# SCH_AOG_Test_Board_2023-11-28.net
KiCad netlist of a schematic drawn in EasyEDA
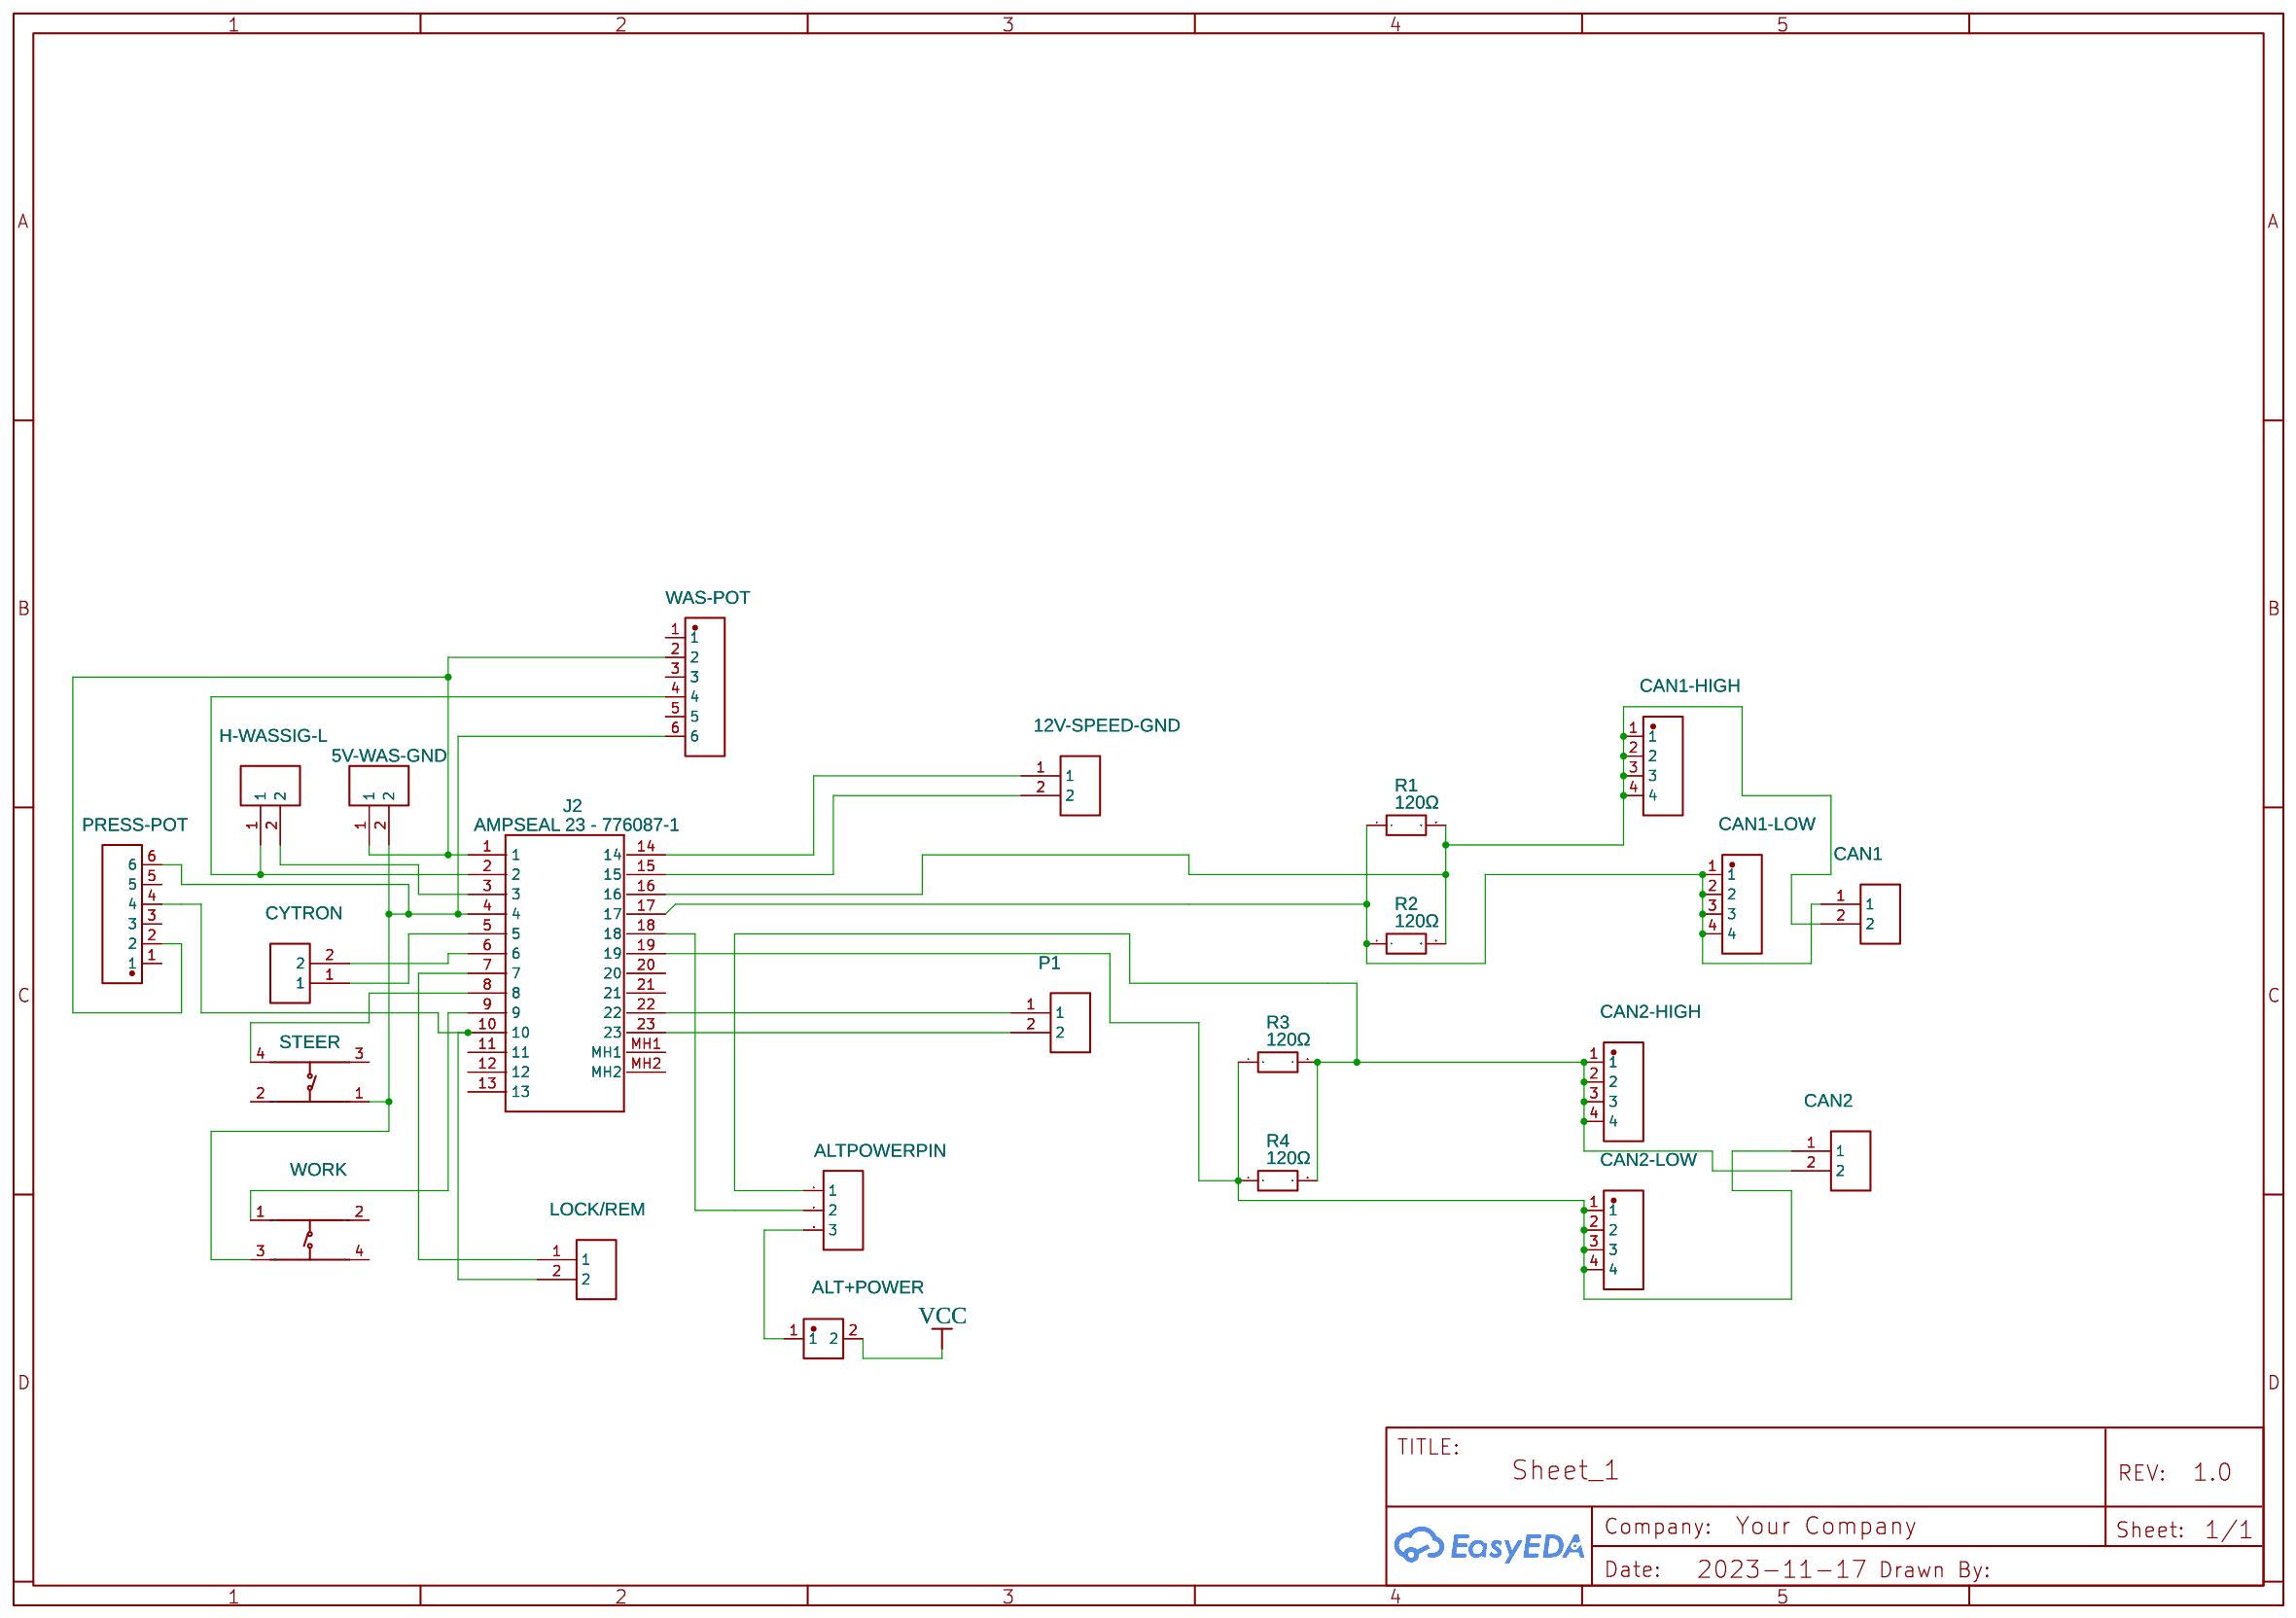
[diagram p0: schematic sheet]

(export (version "E")
  (design (tool "Eeschema 10.0.6"))
  (components
    (comp (ref "5V-WAS-GND")
      (value "WJ500V-5.08-2P-14-00A")
      (fields
        (field (name "Manufacturer Part") "WJ500V-5.08-2P")
        (field (name "Manufacturer") "KANGNEX(康奈克斯电气)")
      )
      (libsource (lib "") (part "WJ500V-5.08-2P-14-00A_3"))
    )
    (comp (ref "12V-SPEED-GND")
      (value "WJ500V-5.08-2P-14-00A")
      (fields
        (field (name "Manufacturer Part") "WJ500V-5.08-2P")
        (field (name "Manufacturer") "KANGNEX(康奈克斯电气)")
      )
      (libsource (lib "") (part "WJ500V-5.08-2P-14-00A_5"))
    )
    (comp (ref "ALT+POWER")
      (value "EST026")
      (fields (field (name "Manufacturer") "xcfuse(旭程)"))
      (libsource (lib "") (part "EST026"))
    )
    (comp (ref "ALTPOWERPIN")
      (value "Header-Male-2.54_1x3")
      (fields (field (name "Manufacturer Part") "2.54-1*3P针") (field (name "Manufacturer") "BOOMELE(博穆精密)"))
      (libsource (lib "") (part "Header-Male-2.54_1x3"))
    )
    (comp (ref "CAN1")
      (value "WJ500V-5.08-2P-14-00A")
      (fields
        (field (name "Manufacturer Part") "WJ500V-5.08-2P")
        (field (name "Manufacturer") "KANGNEX(康奈克斯电气)")
      )
      (libsource (lib "") (part "WJ500V-5.08-2P-14-00A_1"))
    )
    (comp (ref "CAN1-HIGH")
      (value "BX-PZ2.54-1-4PZZ")
      (fields (field (name "Manufacturer") "Bossie(博锡)"))
      (libsource (lib "") (part "BX-PZ2.54-1-4PZZ"))
    )
    (comp (ref "CAN1-LOW")
      (value "BX-PZ2.54-1-4PZZ")
      (fields (field (name "Manufacturer") "Bossie(博锡)"))
      (libsource (lib "") (part "BX-PZ2.54-1-4PZZ_3"))
    )
    (comp (ref "CAN2")
      (value "WJ500V-5.08-2P-14-00A")
      (fields
        (field (name "Manufacturer Part") "WJ500V-5.08-2P")
        (field (name "Manufacturer") "KANGNEX(康奈克斯电气)")
      )
      (libsource (lib "") (part "WJ500V-5.08-2P-14-00A_1"))
    )
    (comp (ref "CAN2-HIGH")
      (value "BX-PZ2.54-1-4PZZ")
      (fields (field (name "Manufacturer") "Bossie(博锡)"))
      (libsource (lib "") (part "BX-PZ2.54-1-4PZZ_1"))
    )
    (comp (ref "CAN2-LOW")
      (value "BX-PZ2.54-1-4PZZ")
      (fields (field (name "Manufacturer") "Bossie(博锡)"))
      (libsource (lib "") (part "BX-PZ2.54-1-4PZZ_2"))
    )
    (comp (ref "CYTRON")
      (value "WJ500V-5.08-2P-14-00A")
      (fields
        (field (name "Manufacturer Part") "WJ500V-5.08-2P")
        (field (name "Manufacturer") "KANGNEX(康奈克斯电气)")
      )
      (libsource (lib "") (part "WJ500V-5.08-2P-14-00A"))
    )
    (comp (ref "H-WASSIG-L")
      (value "WJ500V-5.08-2P-14-00A")
      (fields
        (field (name "Manufacturer Part") "WJ500V-5.08-2P")
        (field (name "Manufacturer") "KANGNEX(康奈克斯电气)")
      )
      (libsource (lib "") (part "WJ500V-5.08-2P-14-00A_6"))
    )
    (comp (ref "J2") (value "AMPSEAL 23 - 776087-1") (libsource (lib "") (part "AMPSEAL 23 - 776087-1")))
    (comp (ref "LOCK/REM")
      (value "WJ500V-5.08-2P-14-00A")
      (fields
        (field (name "Manufacturer Part") "WJ500V-5.08-2P")
        (field (name "Manufacturer") "KANGNEX(康奈克斯电气)")
      )
      (libsource (lib "") (part "WJ500V-5.08-2P-14-00A_4"))
    )
    (comp (ref "P1")
      (value "WJ500V-5.08-2P-14-00A")
      (fields
        (field (name "Manufacturer Part") "WJ500V-5.08-2P")
        (field (name "Manufacturer") "KANGNEX(康奈克斯电气)")
      )
      (libsource (lib "") (part "WJ500V-5.08-2P-14-00A_2"))
    )
    (comp (ref "PRESS-POT")
      (value "Header-Female-2.54_1x6")
      (fields (field (name "Manufacturer Part") "2.54-1*6P母") (field (name "Manufacturer") "BOOMELE(博穆精密)"))
      (libsource (lib "") (part "Header-Female-2.54_1x6_1"))
    )
    (comp (ref "R1")
      (value "120Ω")
      (fields
        (field (name "Manufacturer Part") "RD 1/4W 120R J T/B A1")
        (field (name "Manufacturer") "Tyohm(幸亚电阻)")
      )
      (libsource (lib "") (part "RD 1/4W 120R J T/B A1"))
    )
    (comp (ref "R2")
      (value "120Ω")
      (fields
        (field (name "Manufacturer Part") "RD 1/4W 120R J T/B A1")
        (field (name "Manufacturer") "Tyohm(幸亚电阻)")
      )
      (libsource (lib "") (part "RD 1/4W 120R J T/B A1"))
    )
    (comp (ref "R3")
      (value "120Ω")
      (fields
        (field (name "Manufacturer Part") "RD 1/4W 120R J T/B A1")
        (field (name "Manufacturer") "Tyohm(幸亚电阻)")
      )
      (libsource (lib "") (part "RD 1/4W 120R J T/B A1"))
    )
    (comp (ref "R4")
      (value "120Ω")
      (fields
        (field (name "Manufacturer Part") "RD 1/4W 120R J T/B A1")
        (field (name "Manufacturer") "Tyohm(幸亚电阻)")
      )
      (libsource (lib "") (part "RD 1/4W 120R J T/B A1"))
    )
    (comp (ref "STEER")
      (value "TS665CJ")
      (fields (field (name "Manufacturer") "SHOU HAN(首韩)"))
      (libsource (lib "") (part "TS665CJ_1"))
    )
    (comp (ref "WAS-POT")
      (value "Header-Female-2.54_1x6")
      (fields (field (name "Manufacturer Part") "2.54-1*6P母") (field (name "Manufacturer") "BOOMELE(博穆精密)"))
      (libsource (lib "") (part "Header-Female-2.54_1x6"))
    )
    (comp (ref "WORK")
      (value "TS665CJ")
      (fields (field (name "Manufacturer") "SHOU HAN(首韩)"))
      (libsource (lib "") (part "TS665CJ"))
    )
  )
  (nets
    (net (code "1") (name "Net-(5V-WAS-GND-Pad1)") (class "Default")
      (node (ref "5V-WAS-GND") (pin "1") (pinfunction "1_1") (pintype "unspecified"))
      (node (ref "J2") (pin "1") (pinfunction "1_1") (pintype "bidirectional"))
      (node (ref "PRESS-POT") (pin "2") (pinfunction "2_2") (pintype "unspecified"))
      (node (ref "WAS-POT") (pin "2") (pinfunction "2_2") (pintype "unspecified"))
    )
    (net (code "2") (name "Net-(12V-SPEED-GND-Pad1)") (class "Default")
      (node (ref "12V-SPEED-GND") (pin "1") (pinfunction "1_1") (pintype "unspecified"))
      (node (ref "J2") (pin "14") (pinfunction "14_14") (pintype "bidirectional"))
    )
    (net (code "3") (name "Net-(12V-SPEED-GND-Pad2)") (class "Default")
      (node (ref "12V-SPEED-GND") (pin "2") (pinfunction "2_2") (pintype "unspecified"))
      (node (ref "J2") (pin "15") (pinfunction "15_15") (pintype "bidirectional"))
    )
    (net (code "4") (name "Net-(ALT+POWER-Pad1)") (class "Default")
      (node (ref "ALT+POWER") (pin "1") (pinfunction "1_1") (pintype "unspecified"))
      (node (ref "ALTPOWERPIN") (pin "3") (pinfunction "3_3") (pintype "input"))
    )
    (net (code "5") (name "Net-(ALTPOWERPIN-Pad1)") (class "Default")
      (node (ref "ALTPOWERPIN") (pin "1") (pinfunction "1_1") (pintype "input"))
      (node (ref "CAN2") (pin "2") (pinfunction "2_2") (pintype "unspecified"))
      (node (ref "CAN2-HIGH") (pin "1") (pinfunction "1_1") (pintype "unspecified"))
      (node (ref "CAN2-HIGH") (pin "2") (pinfunction "2_2") (pintype "unspecified"))
      (node (ref "CAN2-HIGH") (pin "3") (pinfunction "3_3") (pintype "unspecified"))
      (node (ref "CAN2-HIGH") (pin "4") (pinfunction "4_4") (pintype "unspecified"))
      (node (ref "R3") (pin "2") (pinfunction "2_2") (pintype "unspecified"))
      (node (ref "R4") (pin "2") (pinfunction "2_2") (pintype "unspecified"))
    )
    (net (code "6") (name "Net-(ALTPOWERPIN-Pad2)") (class "Default")
      (node (ref "ALTPOWERPIN") (pin "2") (pinfunction "2_2") (pintype "input"))
      (node (ref "J2") (pin "18") (pinfunction "18_18") (pintype "bidirectional"))
    )
    (net (code "7") (name "Net-(CAN1-HIGH-Pad1)") (class "Default")
      (node (ref "CAN1") (pin "2") (pinfunction "2_2") (pintype "unspecified"))
      (node (ref "CAN1-HIGH") (pin "1") (pinfunction "1_1") (pintype "unspecified"))
      (node (ref "CAN1-HIGH") (pin "2") (pinfunction "2_2") (pintype "unspecified"))
      (node (ref "CAN1-HIGH") (pin "3") (pinfunction "3_3") (pintype "unspecified"))
      (node (ref "CAN1-HIGH") (pin "4") (pinfunction "4_4") (pintype "unspecified"))
      (node (ref "J2") (pin "16") (pinfunction "16_16") (pintype "bidirectional"))
      (node (ref "R1") (pin "2") (pinfunction "2_2") (pintype "unspecified"))
      (node (ref "R2") (pin "2") (pinfunction "2_2") (pintype "unspecified"))
    )
    (net (code "8") (name "Net-(CAN1-LOW-Pad1)") (class "Default")
      (node (ref "CAN1") (pin "1") (pinfunction "1_1") (pintype "unspecified"))
      (node (ref "CAN1-LOW") (pin "1") (pinfunction "1_1") (pintype "unspecified"))
      (node (ref "CAN1-LOW") (pin "2") (pinfunction "2_2") (pintype "unspecified"))
      (node (ref "CAN1-LOW") (pin "3") (pinfunction "3_3") (pintype "unspecified"))
      (node (ref "CAN1-LOW") (pin "4") (pinfunction "4_4") (pintype "unspecified"))
      (node (ref "J2") (pin "17") (pinfunction "17_17") (pintype "bidirectional"))
      (node (ref "R1") (pin "1") (pinfunction "1_1") (pintype "unspecified"))
      (node (ref "R2") (pin "1") (pinfunction "1_1") (pintype "unspecified"))
    )
    (net (code "9") (name "Net-(CAN2-LOW-Pad1)") (class "Default")
      (node (ref "CAN2") (pin "1") (pinfunction "1_1") (pintype "unspecified"))
      (node (ref "CAN2-LOW") (pin "1") (pinfunction "1_1") (pintype "unspecified"))
      (node (ref "CAN2-LOW") (pin "2") (pinfunction "2_2") (pintype "unspecified"))
      (node (ref "CAN2-LOW") (pin "3") (pinfunction "3_3") (pintype "unspecified"))
      (node (ref "CAN2-LOW") (pin "4") (pinfunction "4_4") (pintype "unspecified"))
      (node (ref "J2") (pin "19") (pinfunction "19_19") (pintype "bidirectional"))
      (node (ref "R3") (pin "1") (pinfunction "1_1") (pintype "unspecified"))
      (node (ref "R4") (pin "1") (pinfunction "1_1") (pintype "unspecified"))
    )
    (net (code "10") (name "Net-(CYTRON-Pad1)") (class "Default")
      (node (ref "CYTRON") (pin "1") (pinfunction "1_1") (pintype "unspecified"))
      (node (ref "J2") (pin "5") (pinfunction "5_5") (pintype "bidirectional"))
    )
    (net (code "11") (name "Net-(CYTRON-Pad2)") (class "Default")
      (node (ref "CYTRON") (pin "2") (pinfunction "2_2") (pintype "unspecified"))
      (node (ref "J2") (pin "6") (pinfunction "6_6") (pintype "bidirectional"))
    )
    (net (code "12") (name "Net-(H-WASSIG-L-Pad1)") (class "Default")
      (node (ref "H-WASSIG-L") (pin "1") (pinfunction "1_1") (pintype "unspecified"))
      (node (ref "J2") (pin "2") (pinfunction "2_2") (pintype "bidirectional"))
      (node (ref "WAS-POT") (pin "4") (pinfunction "4_4") (pintype "unspecified"))
    )
    (net (code "13") (name "Net-(H-WASSIG-L-Pad2)") (class "Default")
      (node (ref "H-WASSIG-L") (pin "2") (pinfunction "2_2") (pintype "unspecified"))
      (node (ref "J2") (pin "3") (pinfunction "3_3") (pintype "bidirectional"))
    )
    (net (code "14") (name "Net-(J2-Pad7)") (class "Default")
      (node (ref "J2") (pin "7") (pinfunction "7_7") (pintype "bidirectional"))
      (node (ref "LOCK/REM") (pin "1") (pinfunction "1_1") (pintype "unspecified"))
    )
    (net (code "15") (name "Net-(J2-Pad10)") (class "Default")
      (node (ref "J2") (pin "10") (pinfunction "10_10") (pintype "bidirectional"))
      (node (ref "LOCK/REM") (pin "2") (pinfunction "2_2") (pintype "unspecified"))
      (node (ref "PRESS-POT") (pin "4") (pinfunction "4_4") (pintype "unspecified"))
    )
    (net (code "16") (name "Net-(J2-Pad22)") (class "Default")
      (node (ref "J2") (pin "22") (pinfunction "22_22") (pintype "bidirectional"))
      (node (ref "P1") (pin "1") (pinfunction "1_1") (pintype "unspecified"))
    )
    (net (code "17") (name "Net-(J2-Pad23)") (class "Default")
      (node (ref "J2") (pin "23") (pinfunction "23_23") (pintype "bidirectional"))
      (node (ref "P1") (pin "2") (pinfunction "2_2") (pintype "unspecified"))
    )
    (net (code "18") (name "Net-(STEER-A)") (class "Default")
      (node (ref "5V-WAS-GND") (pin "2") (pinfunction "2_2") (pintype "unspecified"))
      (node (ref "J2") (pin "4") (pinfunction "4_4") (pintype "bidirectional"))
      (node (ref "PRESS-POT") (pin "6") (pinfunction "6_6") (pintype "unspecified"))
      (node (ref "STEER") (pin "1") (pinfunction "A_1") (pintype "unspecified"))
      (node (ref "WAS-POT") (pin "6") (pinfunction "6_6") (pintype "unspecified"))
      (node (ref "WORK") (pin "3") (pinfunction "C_3") (pintype "unspecified"))
    )
    (net (code "19") (name "Net-(STEER-D)") (class "Default")
      (node (ref "J2") (pin "8") (pinfunction "8_8") (pintype "bidirectional"))
      (node (ref "STEER") (pin "4") (pinfunction "D_4") (pintype "unspecified"))
    )
    (net (code "20") (name "Net-(WORK-A)") (class "Default")
      (node (ref "J2") (pin "9") (pinfunction "9_9") (pintype "bidirectional"))
      (node (ref "WORK") (pin "1") (pinfunction "A_1") (pintype "unspecified"))
    )
    (net (code "21") (name "VCC") (class "Default")
      (node (ref "ALT+POWER") (pin "2") (pinfunction "2_2") (pintype "unspecified"))
    )
    (net (code "22") (name "unconnected-(J2-Pad11)") (class "Default")
      (node (ref "J2") (pin "11") (pinfunction "11_11") (pintype "bidirectional"))
    )
    (net (code "23") (name "unconnected-(J2-Pad12)") (class "Default")
      (node (ref "J2") (pin "12") (pinfunction "12_12") (pintype "bidirectional"))
    )
    (net (code "24") (name "unconnected-(J2-Pad13)") (class "Default")
      (node (ref "J2") (pin "13") (pinfunction "13_13") (pintype "bidirectional"))
    )
    (net (code "25") (name "unconnected-(J2-Pad20)") (class "Default")
      (node (ref "J2") (pin "20") (pinfunction "20_20") (pintype "bidirectional"))
    )
    (net (code "26") (name "unconnected-(J2-Pad21)") (class "Default")
      (node (ref "J2") (pin "21") (pinfunction "21_21") (pintype "bidirectional"))
    )
    (net (code "27") (name "unconnected-(J2-PadMH1)") (class "Default")
      (node (ref "J2") (pin "MH1") (pinfunction "MH1_MH1") (pintype "bidirectional"))
    )
    (net (code "28") (name "unconnected-(J2-PadMH2)") (class "Default")
      (node (ref "J2") (pin "MH2") (pinfunction "MH2_MH2") (pintype "bidirectional"))
    )
    (net (code "29") (name "unconnected-(PRESS-POT-Pad1)") (class "Default")
      (node (ref "PRESS-POT") (pin "1") (pinfunction "1_1") (pintype "unspecified"))
    )
    (net (code "30") (name "unconnected-(PRESS-POT-Pad3)") (class "Default")
      (node (ref "PRESS-POT") (pin "3") (pinfunction "3_3") (pintype "unspecified"))
    )
    (net (code "31") (name "unconnected-(PRESS-POT-Pad5)") (class "Default")
      (node (ref "PRESS-POT") (pin "5") (pinfunction "5_5") (pintype "unspecified"))
    )
    (net (code "32") (name "unconnected-(STEER-B-Pad2)") (class "Default")
      (node (ref "STEER") (pin "2") (pinfunction "B_2") (pintype "unspecified"))
    )
    (net (code "33") (name "unconnected-(STEER-C-Pad3)") (class "Default")
      (node (ref "STEER") (pin "3") (pinfunction "C_3") (pintype "unspecified"))
    )
    (net (code "34") (name "unconnected-(WAS-POT-Pad1)") (class "Default")
      (node (ref "WAS-POT") (pin "1") (pinfunction "1_1") (pintype "unspecified"))
    )
    (net (code "35") (name "unconnected-(WAS-POT-Pad3)") (class "Default")
      (node (ref "WAS-POT") (pin "3") (pinfunction "3_3") (pintype "unspecified"))
    )
    (net (code "36") (name "unconnected-(WAS-POT-Pad5)") (class "Default")
      (node (ref "WAS-POT") (pin "5") (pinfunction "5_5") (pintype "unspecified"))
    )
    (net (code "37") (name "unconnected-(WORK-B-Pad2)") (class "Default")
      (node (ref "WORK") (pin "2") (pinfunction "B_2") (pintype "unspecified"))
    )
    (net (code "38") (name "unconnected-(WORK-D-Pad4)") (class "Default")
      (node (ref "WORK") (pin "4") (pinfunction "D_4") (pintype "unspecified"))
    )
  )
)
